# Master_Micro_Circuit_Manual.net
KiCad netlist of a schematic drawn in EAGLE
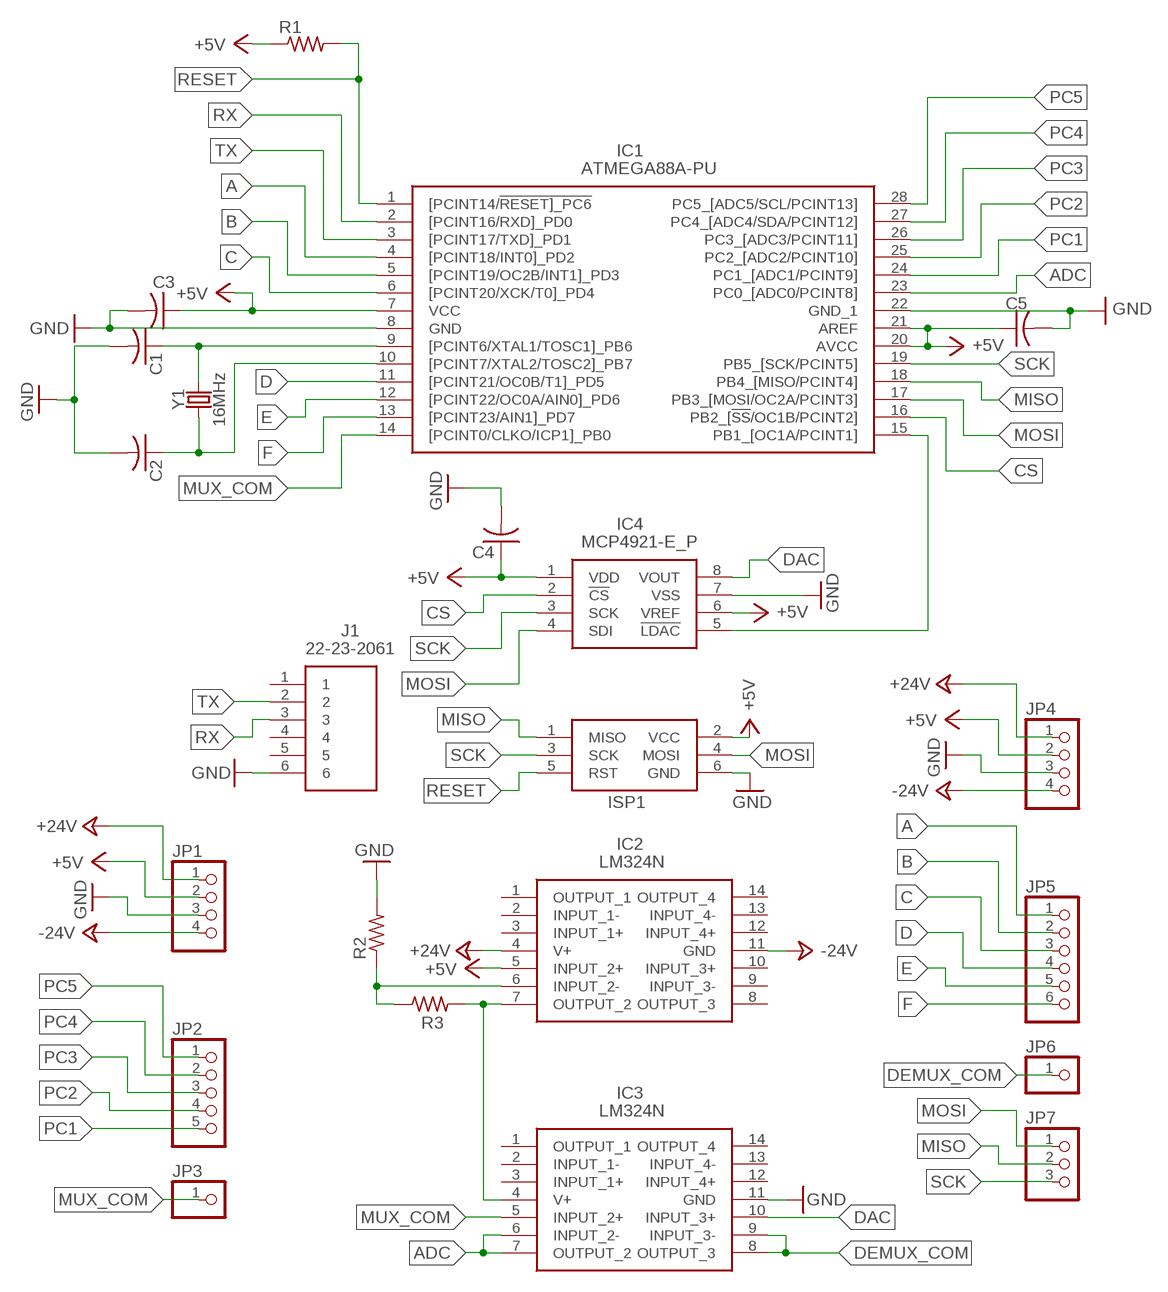
[diagram p0: schematic, sheet 1]

(export (version "E")
  (design (tool "Eeschema 10.0.6"))
  (components
    (comp (ref "C1")
      (value "C-US050-030X075")
      (footprint "eagle-import:C050-030X075")
      (libsource (lib "eagle-import") (part "C-US050-030X075"))
    )
    (comp (ref "C2")
      (value "C-US050-030X075")
      (footprint "eagle-import:C050-030X075")
      (libsource (lib "eagle-import") (part "C-US050-030X075"))
    )
    (comp (ref "C3")
      (value "C-US050-030X075")
      (footprint "eagle-import:C050-030X075")
      (libsource (lib "eagle-import") (part "C-US050-030X075"))
    )
    (comp (ref "C4")
      (value "C-US050-030X075")
      (footprint "eagle-import:C050-030X075")
      (libsource (lib "eagle-import") (part "C-US050-030X075"))
    )
    (comp (ref "C5")
      (value "C-US050-030X075")
      (footprint "eagle-import:C050-030X075")
      (libsource (lib "eagle-import") (part "C-US050-030X075"))
    )
    (comp (ref "IC1")
      (value "ATMEGA88A-PU")
      (footprint "eagle-import:DIP794W53P254L3467H457Q28N")
      (fields (field (name "MOUSER_PART_NUMBER") "556-ATMEGA88A-PU"))
      (libsource (lib "eagle-import") (part "ATMEGA88A-PU"))
    )
    (comp (ref "IC2")
      (value "LM324N")
      (footprint "eagle-import:DIP794W56P254L1905H533Q14N")
      (fields (field (name "MOUSER_PART_NUMBER") "595-LM324N"))
      (libsource (lib "eagle-import") (part "LM324N"))
    )
    (comp (ref "IC3")
      (value "LM324N")
      (footprint "eagle-import:DIP794W56P254L1905H533Q14N")
      (fields (field (name "MOUSER_PART_NUMBER") "595-LM324N"))
      (libsource (lib "eagle-import") (part "LM324N"))
    )
    (comp (ref "IC4")
      (value "MCP4921-E_P")
      (footprint "eagle-import:DIP781W56P254L950H533Q8N")
      (fields
        (field (name "MANUFACTURER_PART_NUMBER") "MCP4921-E/P")
        (field (name "MOUSER_PART_NUMBER") "579-MCP4921-E/P")
      )
      (libsource (lib "eagle-import") (part "MCP4921-E_P"))
    )
    (comp (ref "ISP1")
      (value "AVRISP-BOX")
      (footprint "eagle-import:AVRISP-BOX")
      (libsource (lib "eagle-import") (part "AVRISP-BOX"))
    )
    (comp (ref "J1")
      (value "22-23-2061")
      (footprint "eagle-import:SHDR6W87P0X254_1X6_1509X635X10")
      (fields (field (name "MOUSER_PART_NUMBER") "538-22-23-2061"))
      (libsource (lib "eagle-import") (part "22-23-2061"))
    )
    (comp (ref "JP1")
      (value "PINHD-1X4")
      (footprint "eagle-import:1X04")
      (libsource (lib "eagle-import") (part "PINHD-1X4"))
    )
    (comp (ref "JP2")
      (value "PINHD-1X5")
      (footprint "eagle-import:1X05")
      (libsource (lib "eagle-import") (part "PINHD-1X5"))
    )
    (comp (ref "JP3")
      (value "PINHD-1X1")
      (footprint "eagle-import:1X01")
      (libsource (lib "eagle-import") (part "PINHD-1X1"))
    )
    (comp (ref "JP4")
      (value "PINHD-1X4")
      (footprint "eagle-import:1X04")
      (libsource (lib "eagle-import") (part "PINHD-1X4"))
    )
    (comp (ref "JP5")
      (value "PINHD-1X6")
      (footprint "eagle-import:1X06")
      (libsource (lib "eagle-import") (part "PINHD-1X6"))
    )
    (comp (ref "JP6")
      (value "PINHD-1X1")
      (footprint "eagle-import:1X01")
      (libsource (lib "eagle-import") (part "PINHD-1X1"))
    )
    (comp (ref "JP7")
      (value "PINHD-1X3")
      (footprint "eagle-import:1X03")
      (libsource (lib "eagle-import") (part "PINHD-1X3"))
    )
    (comp (ref "R1")
      (value "R-US_0207/10")
      (footprint "eagle-import:0207_10")
      (libsource (lib "eagle-import") (part "R-US_0207/10"))
    )
    (comp (ref "R2")
      (value "R-US_0207/10")
      (footprint "eagle-import:0207_10")
      (libsource (lib "eagle-import") (part "R-US_0207/10"))
    )
    (comp (ref "R3")
      (value "R-US_0207/10")
      (footprint "eagle-import:0207_10")
      (libsource (lib "eagle-import") (part "R-US_0207/10"))
    )
    (comp (ref "Y1")
      (value "16MHz")
      (footprint "eagle-import:HC49US")
      (libsource (lib "eagle-import") (part "CRYSTAL-16MHZPTH-HC49US"))
    )
  )
  (nets
    (net (code "1") (name "+5V") (class "Default")
      (node (ref "C3") (pin "1") (pinfunction "1_1") (pintype "passive"))
      (node (ref "C4") (pin "1") (pinfunction "1_1") (pintype "passive"))
      (node (ref "C5") (pin "1") (pinfunction "1_1") (pintype "passive"))
      (node (ref "IC1") (pin "20") (pinfunction "AVCC_20") (pintype "power_in"))
      (node (ref "IC1") (pin "21") (pinfunction "AREF_21") (pintype "input"))
      (node (ref "IC1") (pin "7") (pinfunction "VCC_7") (pintype "power_in"))
      (node (ref "IC2") (pin "5") (pinfunction "INPUT_2+_5") (pintype "bidirectional"))
      (node (ref "IC4") (pin "1") (pinfunction "VDD_1") (pintype "power_in"))
      (node (ref "IC4") (pin "6") (pinfunction "VREF_6") (pintype "input"))
      (node (ref "ISP1") (pin "2") (pinfunction "VCC_2") (pintype "power_in"))
      (node (ref "JP1") (pin "2") (pinfunction "2_2") (pintype "passive"))
      (node (ref "JP4") (pin "2") (pinfunction "2_2") (pintype "passive"))
      (node (ref "R1") (pin "1") (pinfunction "1_1") (pintype "passive"))
    )
    (net (code "2") (name "+24V") (class "Default")
      (node (ref "IC2") (pin "4") (pinfunction "V+_4") (pintype "bidirectional"))
      (node (ref "JP1") (pin "1") (pinfunction "1_1") (pintype "passive"))
      (node (ref "JP4") (pin "1") (pinfunction "1_1") (pintype "passive"))
    )
    (net (code "3") (name "-24V") (class "Default")
      (node (ref "IC2") (pin "11") (pinfunction "GND_11") (pintype "bidirectional"))
      (node (ref "JP1") (pin "4") (pinfunction "4_4") (pintype "passive"))
      (node (ref "JP4") (pin "4") (pinfunction "4_4") (pintype "passive"))
    )
    (net (code "4") (name "A") (class "Default")
      (node (ref "IC1") (pin "4") (pinfunction "[PCINT18/INT0]_PD2_4") (pintype "input"))
      (node (ref "JP5") (pin "1") (pinfunction "1_1") (pintype "passive"))
    )
    (net (code "5") (name "ADC") (class "Default")
      (node (ref "IC1") (pin "23") (pinfunction "PC0_[ADC0/PCINT8]_23") (pintype "input"))
      (node (ref "IC3") (pin "6") (pinfunction "INPUT_2-_6") (pintype "bidirectional"))
      (node (ref "IC3") (pin "7") (pinfunction "OUTPUT_2_7") (pintype "bidirectional"))
    )
    (net (code "6") (name "B") (class "Default")
      (node (ref "IC1") (pin "5") (pinfunction "[PCINT19/OC2B/INT1]_PD3_5") (pintype "input"))
      (node (ref "JP5") (pin "2") (pinfunction "2_2") (pintype "passive"))
    )
    (net (code "7") (name "C") (class "Default")
      (node (ref "IC1") (pin "6") (pinfunction "[PCINT20/XCK/T0]_PD4_6") (pintype "input"))
      (node (ref "JP5") (pin "3") (pinfunction "3_3") (pintype "passive"))
    )
    (net (code "8") (name "CS") (class "Default")
      (node (ref "IC1") (pin "16") (pinfunction "PB2_[~{SS}/OC1B/PCINT2]_16") (pintype "input"))
      (node (ref "IC4") (pin "2") (pinfunction "~{CS}_2") (pintype "input"))
    )
    (net (code "9") (name "D") (class "Default")
      (node (ref "IC1") (pin "11") (pinfunction "[PCINT21/OC0B/T1]_PD5_11") (pintype "input"))
      (node (ref "JP5") (pin "4") (pinfunction "4_4") (pintype "passive"))
    )
    (net (code "10") (name "DAC") (class "Default")
      (node (ref "IC3") (pin "10") (pinfunction "INPUT_3+_10") (pintype "bidirectional"))
      (node (ref "IC4") (pin "8") (pinfunction "VOUT_8") (pintype "output"))
    )
    (net (code "11") (name "DEMUX_COM") (class "Default")
      (node (ref "IC3") (pin "8") (pinfunction "OUTPUT_3_8") (pintype "bidirectional"))
      (node (ref "IC3") (pin "9") (pinfunction "INPUT_3-_9") (pintype "bidirectional"))
      (node (ref "JP6") (pin "1") (pinfunction "1_1") (pintype "passive"))
    )
    (net (code "12") (name "E") (class "Default")
      (node (ref "IC1") (pin "12") (pinfunction "[PCINT22/OC0A/AIN0]_PD6_12") (pintype "input"))
      (node (ref "JP5") (pin "5") (pinfunction "5_5") (pintype "passive"))
    )
    (net (code "13") (name "F") (class "Default")
      (node (ref "IC1") (pin "13") (pinfunction "[PCINT23/AIN1]_PD7_13") (pintype "input"))
      (node (ref "JP5") (pin "6") (pinfunction "6_6") (pintype "passive"))
    )
    (net (code "14") (name "GND") (class "Default")
      (node (ref "C1") (pin "2") (pinfunction "2_2") (pintype "passive"))
      (node (ref "C2") (pin "2") (pinfunction "2_2") (pintype "passive"))
      (node (ref "C3") (pin "2") (pinfunction "2_2") (pintype "passive"))
      (node (ref "C4") (pin "2") (pinfunction "2_2") (pintype "passive"))
      (node (ref "C5") (pin "2") (pinfunction "2_2") (pintype "passive"))
      (node (ref "IC1") (pin "22") (pinfunction "GND_1_22") (pintype "power_in"))
      (node (ref "IC1") (pin "8") (pinfunction "GND_8") (pintype "power_in"))
      (node (ref "IC3") (pin "11") (pinfunction "GND_11") (pintype "bidirectional"))
      (node (ref "IC4") (pin "7") (pinfunction "VSS_7") (pintype "power_in"))
      (node (ref "ISP1") (pin "6") (pinfunction "GND_6") (pintype "power_in"))
      (node (ref "J1") (pin "6") (pinfunction "6_6") (pintype "bidirectional"))
      (node (ref "JP1") (pin "3") (pinfunction "3_3") (pintype "passive"))
      (node (ref "JP4") (pin "3") (pinfunction "3_3") (pintype "passive"))
      (node (ref "R2") (pin "2") (pinfunction "2_2") (pintype "passive"))
    )
    (net (code "15") (name "MISO") (class "Default")
      (node (ref "IC1") (pin "18") (pinfunction "PB4_[MISO/PCINT4]_18") (pintype "input"))
      (node (ref "ISP1") (pin "1") (pinfunction "MISO_1") (pintype "input"))
      (node (ref "JP7") (pin "2") (pinfunction "2_2") (pintype "passive"))
    )
    (net (code "16") (name "MOSI") (class "Default")
      (node (ref "IC1") (pin "17") (pinfunction "PB3_[MOSI/OC2A/PCINT3]_17") (pintype "bidirectional"))
      (node (ref "IC4") (pin "4") (pinfunction "SDI_4") (pintype "bidirectional"))
      (node (ref "ISP1") (pin "4") (pinfunction "MOSI_4") (pintype "output"))
      (node (ref "JP7") (pin "1") (pinfunction "1_1") (pintype "passive"))
    )
    (net (code "17") (name "MUX_COM") (class "Default")
      (node (ref "IC1") (pin "14") (pinfunction "[PCINT0/CLKO/ICP1]_PB0_14") (pintype "output"))
      (node (ref "IC3") (pin "5") (pinfunction "INPUT_2+_5") (pintype "bidirectional"))
      (node (ref "JP3") (pin "1") (pinfunction "1_1") (pintype "passive"))
    )
    (net (code "18") (name "Net-(IC1-PB1_[OC1A{slash}PCINT1])") (class "Default")
      (node (ref "IC1") (pin "15") (pinfunction "PB1_[OC1A/PCINT1]_15") (pintype "input"))
      (node (ref "IC4") (pin "5") (pinfunction "~{LDAC}_5") (pintype "bidirectional"))
    )
    (net (code "19") (name "Net-(IC1-[PCINT6{slash}XTAL1{slash}TOSC1]_PB6)") (class "Default")
      (node (ref "C1") (pin "1") (pinfunction "1_1") (pintype "passive"))
      (node (ref "IC1") (pin "9") (pinfunction "[PCINT6/XTAL1/TOSC1]_PB6_9") (pintype "input"))
      (node (ref "Y1") (pin "2") (pinfunction "2_2") (pintype "passive"))
    )
    (net (code "20") (name "Net-(IC1-[PCINT7{slash}XTAL2{slash}TOSC2]_PB7)") (class "Default")
      (node (ref "C2") (pin "1") (pinfunction "1_1") (pintype "passive"))
      (node (ref "IC1") (pin "10") (pinfunction "[PCINT7/XTAL2/TOSC2]_PB7_10") (pintype "input"))
      (node (ref "Y1") (pin "1") (pinfunction "1_1") (pintype "passive"))
    )
    (net (code "21") (name "Net-(IC2-INPUT_2-)") (class "Default")
      (node (ref "IC2") (pin "6") (pinfunction "INPUT_2-_6") (pintype "bidirectional"))
      (node (ref "R2") (pin "1") (pinfunction "1_1") (pintype "passive"))
      (node (ref "R3") (pin "1") (pinfunction "1_1") (pintype "passive"))
    )
    (net (code "22") (name "Net-(IC2-OUTPUT_2)") (class "Default")
      (node (ref "IC2") (pin "7") (pinfunction "OUTPUT_2_7") (pintype "bidirectional"))
      (node (ref "IC3") (pin "4") (pinfunction "V+_4") (pintype "bidirectional"))
      (node (ref "R3") (pin "2") (pinfunction "2_2") (pintype "passive"))
    )
    (net (code "23") (name "PC1") (class "Default")
      (node (ref "IC1") (pin "24") (pinfunction "PC1_[ADC1/PCINT9]_24") (pintype "input"))
      (node (ref "JP2") (pin "5") (pinfunction "5_5") (pintype "passive"))
    )
    (net (code "24") (name "PC2") (class "Default")
      (node (ref "IC1") (pin "25") (pinfunction "PC2_[ADC2/PCINT10]_25") (pintype "input"))
      (node (ref "JP2") (pin "4") (pinfunction "4_4") (pintype "passive"))
    )
    (net (code "25") (name "PC3") (class "Default")
      (node (ref "IC1") (pin "26") (pinfunction "PC3_[ADC3/PCINT11]_26") (pintype "input"))
      (node (ref "JP2") (pin "3") (pinfunction "3_3") (pintype "passive"))
    )
    (net (code "26") (name "PC4") (class "Default")
      (node (ref "IC1") (pin "27") (pinfunction "PC4_[ADC4/SDA/PCINT12]_27") (pintype "input"))
      (node (ref "JP2") (pin "2") (pinfunction "2_2") (pintype "passive"))
    )
    (net (code "27") (name "PC5") (class "Default")
      (node (ref "IC1") (pin "28") (pinfunction "PC5_[ADC5/SCL/PCINT13]_28") (pintype "input"))
      (node (ref "JP2") (pin "1") (pinfunction "1_1") (pintype "passive"))
    )
    (net (code "28") (name "RESET") (class "Default")
      (node (ref "IC1") (pin "1") (pinfunction "[PCINT14/~{RESET]_PC6}_1") (pintype "input"))
      (node (ref "ISP1") (pin "5") (pinfunction "RST_5") (pintype "output"))
      (node (ref "R1") (pin "2") (pinfunction "2_2") (pintype "passive"))
    )
    (net (code "29") (name "RX") (class "Default")
      (node (ref "IC1") (pin "2") (pinfunction "[PCINT16/RXD]_PD0_2") (pintype "input"))
      (node (ref "J1") (pin "3") (pinfunction "3_3") (pintype "bidirectional"))
    )
    (net (code "30") (name "SCK") (class "Default")
      (node (ref "IC1") (pin "19") (pinfunction "PB5_[SCK/PCINT5]_19") (pintype "input"))
      (node (ref "IC4") (pin "3") (pinfunction "SCK_3") (pintype "bidirectional"))
      (node (ref "ISP1") (pin "3") (pinfunction "SCK_3") (pintype "output"))
      (node (ref "JP7") (pin "3") (pinfunction "3_3") (pintype "passive"))
    )
    (net (code "31") (name "TX") (class "Default")
      (node (ref "IC1") (pin "3") (pinfunction "[PCINT17/TXD]_PD1_3") (pintype "input"))
      (node (ref "J1") (pin "2") (pinfunction "2_2") (pintype "bidirectional"))
    )
    (net (code "32") (name "unconnected-(IC2-INPUT_1+-Pad3)") (class "Default")
      (node (ref "IC2") (pin "3") (pinfunction "INPUT_1+_3") (pintype "bidirectional"))
    )
    (net (code "33") (name "unconnected-(IC2-INPUT_1--Pad2)") (class "Default")
      (node (ref "IC2") (pin "2") (pinfunction "INPUT_1-_2") (pintype "bidirectional"))
    )
    (net (code "34") (name "unconnected-(IC2-INPUT_3+-Pad10)") (class "Default")
      (node (ref "IC2") (pin "10") (pinfunction "INPUT_3+_10") (pintype "bidirectional"))
    )
    (net (code "35") (name "unconnected-(IC2-INPUT_3--Pad9)") (class "Default")
      (node (ref "IC2") (pin "9") (pinfunction "INPUT_3-_9") (pintype "bidirectional"))
    )
    (net (code "36") (name "unconnected-(IC2-INPUT_4+-Pad12)") (class "Default")
      (node (ref "IC2") (pin "12") (pinfunction "INPUT_4+_12") (pintype "bidirectional"))
    )
    (net (code "37") (name "unconnected-(IC2-INPUT_4--Pad13)") (class "Default")
      (node (ref "IC2") (pin "13") (pinfunction "INPUT_4-_13") (pintype "bidirectional"))
    )
    (net (code "38") (name "unconnected-(IC2-OUTPUT_1-Pad1)") (class "Default")
      (node (ref "IC2") (pin "1") (pinfunction "OUTPUT_1_1") (pintype "bidirectional"))
    )
    (net (code "39") (name "unconnected-(IC2-OUTPUT_3-Pad8)") (class "Default")
      (node (ref "IC2") (pin "8") (pinfunction "OUTPUT_3_8") (pintype "bidirectional"))
    )
    (net (code "40") (name "unconnected-(IC2-OUTPUT_4-Pad14)") (class "Default")
      (node (ref "IC2") (pin "14") (pinfunction "OUTPUT_4_14") (pintype "bidirectional"))
    )
    (net (code "41") (name "unconnected-(IC3-INPUT_1+-Pad3)") (class "Default")
      (node (ref "IC3") (pin "3") (pinfunction "INPUT_1+_3") (pintype "bidirectional"))
    )
    (net (code "42") (name "unconnected-(IC3-INPUT_1--Pad2)") (class "Default")
      (node (ref "IC3") (pin "2") (pinfunction "INPUT_1-_2") (pintype "bidirectional"))
    )
    (net (code "43") (name "unconnected-(IC3-INPUT_4+-Pad12)") (class "Default")
      (node (ref "IC3") (pin "12") (pinfunction "INPUT_4+_12") (pintype "bidirectional"))
    )
    (net (code "44") (name "unconnected-(IC3-INPUT_4--Pad13)") (class "Default")
      (node (ref "IC3") (pin "13") (pinfunction "INPUT_4-_13") (pintype "bidirectional"))
    )
    (net (code "45") (name "unconnected-(IC3-OUTPUT_1-Pad1)") (class "Default")
      (node (ref "IC3") (pin "1") (pinfunction "OUTPUT_1_1") (pintype "bidirectional"))
    )
    (net (code "46") (name "unconnected-(IC3-OUTPUT_4-Pad14)") (class "Default")
      (node (ref "IC3") (pin "14") (pinfunction "OUTPUT_4_14") (pintype "bidirectional"))
    )
    (net (code "47") (name "unconnected-(J1-Pad1)") (class "Default")
      (node (ref "J1") (pin "1") (pinfunction "1_1") (pintype "bidirectional"))
    )
    (net (code "48") (name "unconnected-(J1-Pad4)") (class "Default")
      (node (ref "J1") (pin "4") (pinfunction "4_4") (pintype "bidirectional"))
    )
    (net (code "49") (name "unconnected-(J1-Pad5)") (class "Default")
      (node (ref "J1") (pin "5") (pinfunction "5_5") (pintype "bidirectional"))
    )
  )
)
